# BOOT0.net
KiCad netlist of a schematic drawn in Altium Designer
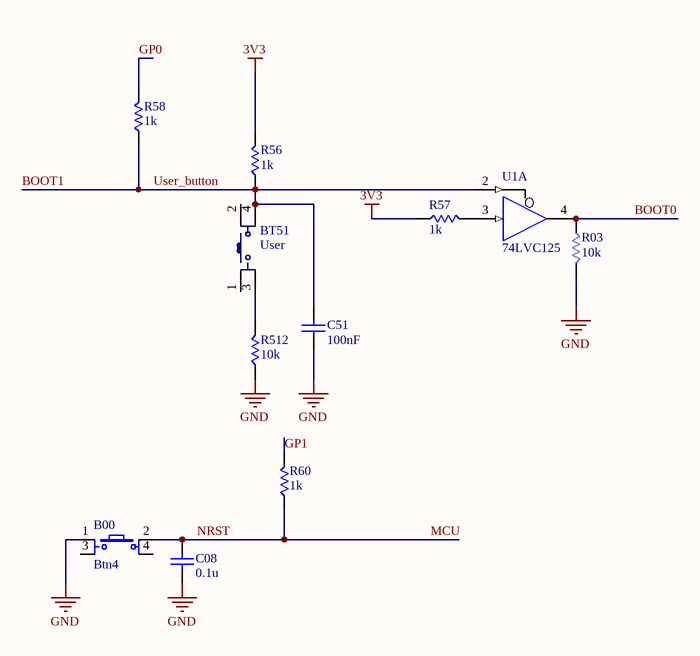
[diagram p0: BOOT0.SchDoc]

(export (version "E")
  (design (tool "Eeschema 10.0.6"))
  (components
    (comp (ref "B00") (value "Btn4") (footprint "Btn-waterproof-smd") (libsource (lib "MyLib") (part "Btn4")))
    (comp (ref "BT51")
      (value "User")
      (footprint "Btn-waterproof-smd")
      (description "Tact switch")
      (libsource (lib "SMD_tact_sw") (part "Button"))
    )
    (comp (ref "C08")
      (value "0.1u")
      (footprint "SM_0805_LD")
      (description "Non-polarity ceramic capacitor")
      (fields (field (name "Comment") "CAP Ceramic") (field (name "PUBLISHER") "Altium Limited"))
      (libsource (lib "HLib_schematic_lib") (part "CAP Ceramic"))
    )
    (comp (ref "C51")
      (value "100nF")
      (footprint "SM_0805_LD")
      (description "Non-polarity ceramic capacitor")
      (fields (field (name "Comment") "C_Ceramic") (field (name "PUBLISHER") "Altium Limited"))
      (libsource (lib "Copy of HLib_device_library") (part "C_Ceramic"))
    )
    (comp (ref "R03")
      (value "10k")
      (footprint "SM_0805_LD")
      (description "Resistor")
      (fields (field (name "Comment") "R") (field (name "PUBLISHER") "Altium Limited"))
      (libsource (lib "HLib_schematic_lib") (part "R"))
    )
    (comp (ref "R56")
      (value "1k")
      (footprint "SM_0805_LD")
      (description "Resistor")
      (fields (field (name "Comment") "R") (field (name "PUBLISHER") "Altium Limited"))
      (libsource (lib "Copy of HLib_device_library") (part "R"))
    )
    (comp (ref "R57")
      (value "1k")
      (footprint "SM_0805_LD")
      (description "Resistor")
      (fields (field (name "Comment") "R") (field (name "PUBLISHER") "Altium Limited"))
      (libsource (lib "Copy of HLib_device_library") (part "R"))
    )
    (comp (ref "R58")
      (value "1k")
      (footprint "SM_0805_LD")
      (description "Resistor")
      (fields (field (name "Comment") "R") (field (name "PUBLISHER") "Altium Limited"))
      (libsource (lib "Copy of HLib_device_library") (part "R"))
    )
    (comp (ref "R60")
      (value "1k")
      (footprint "SM_0805_LD")
      (description "Resistor")
      (fields (field (name "Comment") "R") (field (name "PUBLISHER") "Altium Limited"))
      (libsource (lib "Copy of HLib_device_library") (part "R"))
    )
    (comp (ref "R512")
      (value "10k")
      (footprint "SM_0805_LD")
      (description "Resistor")
      (fields (field (name "Comment") "R") (field (name "PUBLISHER") "Altium Limited"))
      (libsource (lib "Copy of HLib_device_library") (part "R"))
    )
    (comp (ref "U1")
      (value "74LVC125")
      (footprint "FK020")
      (description "Quadruple Bus Buffer Gate with 3-State Outputs")
      (fields (field (name "PUBLISHER") "Altium Limited"))
      (libsource (lib "TI Logic Buffer Line Driver") (part "SN54BCT125AFK"))
    )
  )
  (nets
    (net (code "1") (name "/BOOT0") (class "Default")
      (node (ref "R03") (pin "1") (pinfunction "1_1") (pintype "passive"))
      (node (ref "U1") (pin "4") (pinfunction "Y_4") (pintype "tri_state"))
    )
    (net (code "2") (name "/BOOT1") (class "Default")
      (node (ref "BT51") (pin "4") (pintype "passive"))
      (node (ref "C51") (pin "2") (pinfunction "2_2") (pintype "passive"))
      (node (ref "R56") (pin "1") (pinfunction "1_1") (pintype "passive"))
      (node (ref "R58") (pin "1") (pinfunction "1_1") (pintype "passive"))
      (node (ref "U1") (pin "2") (pinfunction "~{OE}_2") (pintype "input"))
    )
    (net (code "3") (name "/GP0") (class "Default")
      (node (ref "R58") (pin "2") (pinfunction "2_2") (pintype "passive"))
    )
    (net (code "4") (name "/GP1") (class "Default")
      (node (ref "R60") (pin "2") (pinfunction "2_2") (pintype "passive"))
    )
    (net (code "5") (name "/MCU") (class "Default")
      (node (ref "B00") (pin "2") (pinfunction "Tab_2") (pintype "passive"))
      (node (ref "C08") (pin "2") (pinfunction "2_2") (pintype "passive"))
      (node (ref "R60") (pin "1") (pinfunction "1_1") (pintype "passive"))
    )
    (net (code "6") (name "3V3") (class "Default")
      (node (ref "R56") (pin "2") (pinfunction "2_2") (pintype "passive"))
      (node (ref "R57") (pin "1") (pinfunction "1_1") (pintype "passive"))
    )
    (net (code "7") (name "GND") (class "Default")
      (node (ref "B00") (pin "1") (pinfunction "Tab_1") (pintype "passive"))
      (node (ref "C08") (pin "1") (pinfunction "1_1") (pintype "passive"))
      (node (ref "C51") (pin "1") (pinfunction "1_1") (pintype "passive"))
      (node (ref "R03") (pin "2") (pinfunction "2_2") (pintype "passive"))
      (node (ref "R512") (pin "1") (pinfunction "1_1") (pintype "passive"))
      (node (ref "U1") (pin "10") (pinfunction "GND_10") (pintype "power_in"))
    )
    (net (code "8") (name "Net-(BT51-Pad3)") (class "Default")
      (node (ref "BT51") (pin "3") (pintype "passive"))
      (node (ref "R512") (pin "2") (pinfunction "2_2") (pintype "passive"))
    )
    (net (code "9") (name "Net-(U1A-A)") (class "Default")
      (node (ref "R57") (pin "2") (pinfunction "2_2") (pintype "passive"))
      (node (ref "U1") (pin "3") (pinfunction "A_3") (pintype "input"))
    )
    (net (code "10") (name "VCC") (class "Default")
      (node (ref "U1") (pin "20") (pinfunction "VCC_20") (pintype "power_in"))
    )
    (net (code "11") (name "unconnected-(B00-Tab-Pad3)") (class "Default")
      (node (ref "B00") (pin "3") (pinfunction "Tab_3") (pintype "passive"))
    )
    (net (code "12") (name "unconnected-(B00-Tab-Pad4)") (class "Default")
      (node (ref "B00") (pin "4") (pinfunction "Tab_4") (pintype "passive"))
    )
    (net (code "13") (name "unconnected-(BT51-Pad1)") (class "Default")
      (node (ref "BT51") (pin "1") (pintype "passive"))
    )
    (net (code "14") (name "unconnected-(BT51-Pad2)") (class "Default")
      (node (ref "BT51") (pin "2") (pintype "passive"))
    )
  )
)
